# RFnetwork.net
KiCad netlist of a schematic drawn in Altium Designer
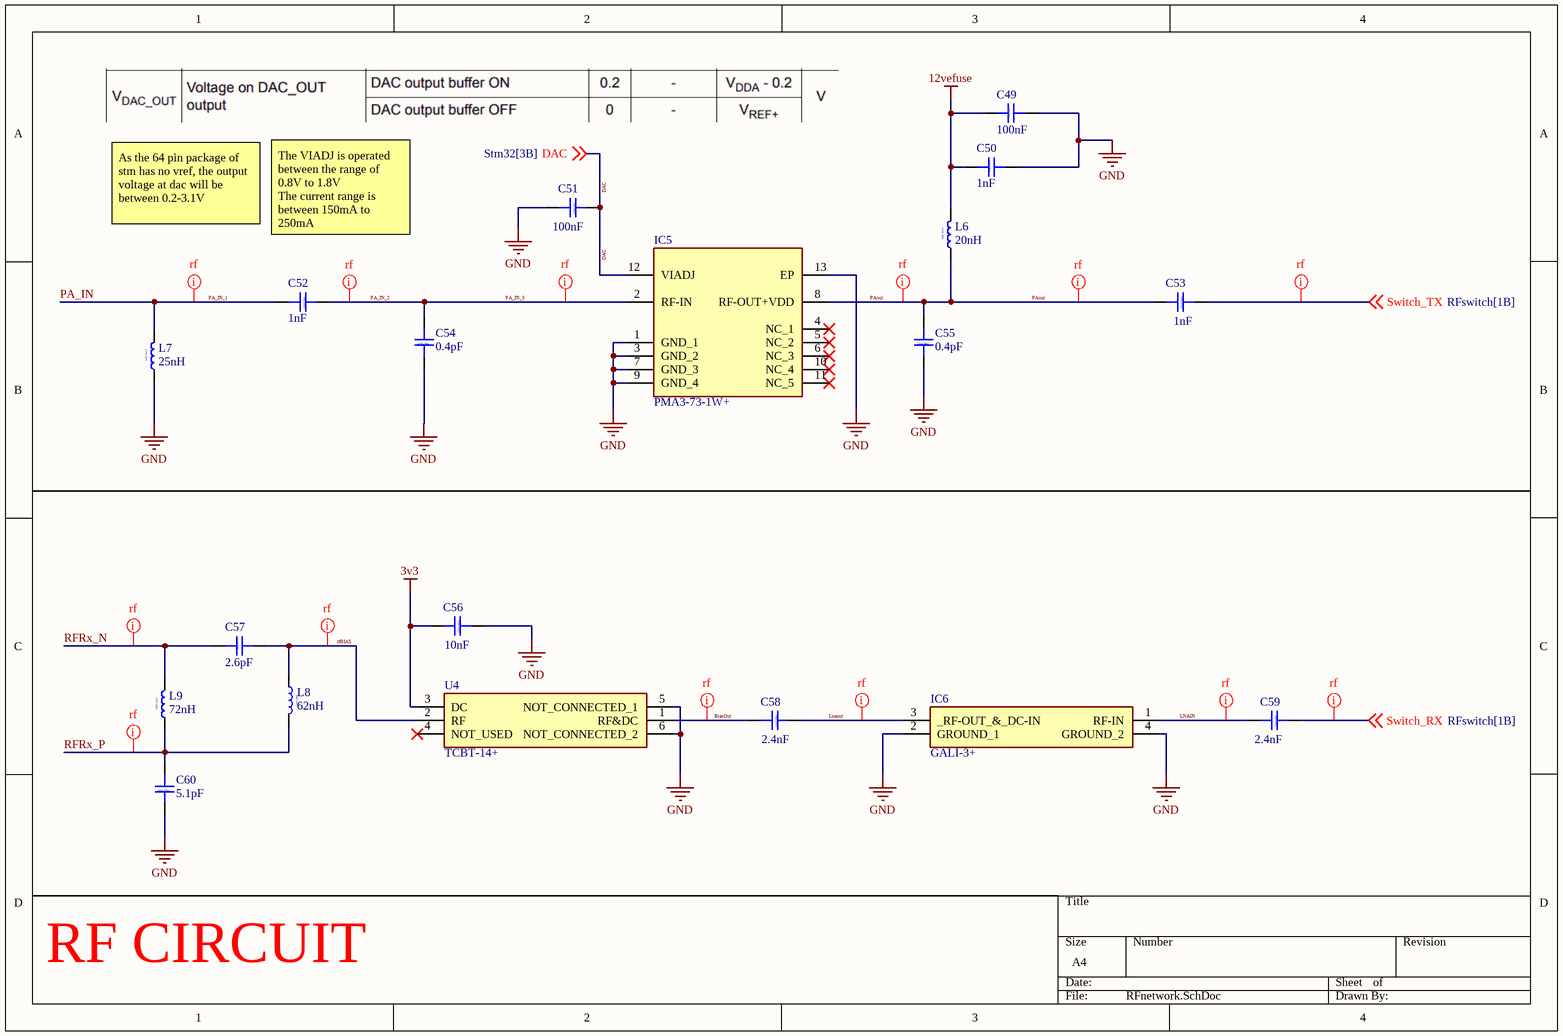
[diagram p0: RFnetwork.SchDoc]

(export (version "E")
  (design (tool "Eeschema 10.0.6"))
  (components
    (comp (ref "C49")
      (value "100nF")
      (footprint "CAP_0603")
      (description "Capacitor SMD 0603 RATED")
      (libsource (lib "STeRG-Passives-Standard") (part "Capacitor-SMD-0603"))
    )
    (comp (ref "C50")
      (value "1nF")
      (footprint "CAP_0603")
      (description "Capacitor SMD 0603 RATED")
      (libsource (lib "STeRG-Passives-Standard") (part "Capacitor-SMD-0603"))
    )
    (comp (ref "C51")
      (value "100nF")
      (footprint "CAP_0603")
      (description "Capacitor SMD 0603 RATED")
      (libsource (lib "STeRG-Passives-Standard") (part "Capacitor-SMD-0603"))
    )
    (comp (ref "C52")
      (value "1nF")
      (footprint "CAP_0603")
      (description "Capacitor SMD 0603 RATED")
      (libsource (lib "STeRG-Passives-Standard") (part "Capacitor-SMD-0603"))
    )
    (comp (ref "C53")
      (value "1nF")
      (footprint "CAP_0603")
      (description "Capacitor SMD 0603 RATED")
      (libsource (lib "STeRG-Passives-Standard") (part "Capacitor-SMD-0603"))
    )
    (comp (ref "C54")
      (value "0.4pF")
      (footprint "CAP_0603")
      (description "Capacitor SMD 0603 RATED")
      (libsource (lib "STeRG-Passives-Standard") (part "Capacitor-SMD-0603"))
    )
    (comp (ref "C55")
      (value "0.4pF")
      (footprint "CAP_0603")
      (description "Capacitor SMD 0603 RATED")
      (libsource (lib "STeRG-Passives-Standard") (part "Capacitor-SMD-0603"))
    )
    (comp (ref "C56")
      (value "10nF")
      (footprint "CAP_0603")
      (description "Capacitor SMD 0603 RATED")
      (libsource (lib "STeRG-Passives-Standard") (part "Capacitor-SMD-0603"))
    )
    (comp (ref "C57")
      (value "2.6pF")
      (footprint "CAP_0402")
      (description "Capacitor SMD 0402 RATED")
      (libsource (lib "STeRG-Passives-Standard") (part "Capacitor-SMD-0402"))
    )
    (comp (ref "C58")
      (value "2.4nF")
      (footprint "CAP_0603")
      (description "Capacitor SMD 0603 RATED")
      (libsource (lib "STeRG-Passives-Standard") (part "Capacitor-SMD-0603"))
    )
    (comp (ref "C59")
      (value "2.4nF")
      (footprint "CAP_0603")
      (description "Capacitor SMD 0603 RATED")
      (libsource (lib "STeRG-Passives-Standard") (part "Capacitor-SMD-0603"))
    )
    (comp (ref "C60")
      (value "5.1pF")
      (footprint "CAP_0402")
      (description "Capacitor SMD 0402 RATED")
      (libsource (lib "STeRG-Passives-Standard") (part "Capacitor-SMD-0402"))
    )
    (comp (ref "IC5")
      (value "PMA3-73-1W+")
      (footprint "SamacSys:QFN51P300X300X89-13N")
      (description "Integrated Circuit")
      (libsource (lib "SamacSys") (part "PMA3-73-1W+"))
    )
    (comp (ref "IC6")
      (value "GALI-3+")
      (footprint "GALI3")
      (description "Integrated Circuit")
      (fields (field (name "MOUSER PART NUMBER") "139-GALI-3"))
      (libsource (lib "SamacSys") (part "GALI-3+"))
    )
    (comp (ref "L6")
      (value "20nH")
      (footprint "IND_0603")
      (description "Inductor SMD 0603")
      (libsource (lib "STeRG-Passives-Standard") (part "Inductor-SMD-RF-0603"))
    )
    (comp (ref "L7")
      (value "25nH")
      (footprint "IND_0603")
      (description "Inductor SMD 0603")
      (libsource (lib "STeRG-Passives-Standard") (part "Inductor-SMD-RF-0603"))
    )
    (comp (ref "L8")
      (value "62nH")
      (footprint "IND_0402")
      (description "Inductor SMD 0402")
      (libsource (lib "STeRG-Passives-Standard") (part "Inductor-SMD-RF-0402"))
    )
    (comp (ref "L9")
      (value "72nH")
      (footprint "IND_0402")
      (description "Inductor SMD 0402")
      (libsource (lib "STeRG-Passives-Standard") (part "Inductor-SMD-RF-0402"))
    )
    (comp (ref "U4")
      (value "TCBT-14+")
      (footprint "TCBT14bias")
      (description "Undefined or Miscellaneous")
      (fields (field (name "MOUSER PART NUMBER") "139-TCBT-14"))
      (libsource (lib "SamacSys") (part "TCBT-14+"))
    )
  )
  (nets
    (net (code "1") (name "/BiasOut") (class "Default")
      (node (ref "C58") (pin "2") (pinfunction "2_2") (pintype "passive"))
      (node (ref "U4") (pin "1") (pinfunction "RF&DC_1") (pintype "passive"))
    )
    (net (code "2") (name "/LNAIN") (class "Default")
      (node (ref "C59") (pin "2") (pinfunction "2_2") (pintype "passive"))
      (node (ref "IC6") (pin "1") (pinfunction "RF-IN_1") (pintype "passive"))
    )
    (net (code "3") (name "/Lnaout") (class "Default")
      (node (ref "C58") (pin "1") (pinfunction "1_1") (pintype "passive"))
      (node (ref "IC6") (pin "3") (pinfunction "_RF-OUT_&_DC-IN_3") (pintype "passive"))
    )
    (net (code "4") (name "/PA_IN") (class "Default")
      (node (ref "C52") (pin "2") (pinfunction "2_2") (pintype "passive"))
      (node (ref "L7") (pin "2") (pinfunction "2_2") (pintype "passive"))
    )
    (net (code "5") (name "/PA_IN_2") (class "Default")
      (node (ref "C52") (pin "1") (pinfunction "1_1") (pintype "passive"))
      (node (ref "C54") (pin "2") (pinfunction "2_2") (pintype "passive"))
      (node (ref "IC5") (pin "2") (pinfunction "RF-IN_2") (pintype "passive"))
    )
    (net (code "6") (name "/PAout") (class "Default")
      (node (ref "C53") (pin "2") (pinfunction "2_2") (pintype "passive"))
      (node (ref "C55") (pin "2") (pinfunction "2_2") (pintype "passive"))
      (node (ref "IC5") (pin "8") (pinfunction "RF-OUT+VDD_8") (pintype "passive"))
      (node (ref "L6") (pin "1") (pinfunction "1_1") (pintype "passive"))
    )
    (net (code "7") (name "/RFRx_N") (class "Default")
      (node (ref "C57") (pin "1") (pinfunction "1_1") (pintype "passive"))
      (node (ref "L9") (pin "2") (pinfunction "2_2") (pintype "passive"))
    )
    (net (code "8") (name "/RFRx_P") (class "Default")
      (node (ref "C60") (pin "2") (pinfunction "2_2") (pintype "passive"))
      (node (ref "L8") (pin "2") (pinfunction "2_2") (pintype "passive"))
      (node (ref "L9") (pin "1") (pinfunction "1_1") (pintype "passive"))
    )
    (net (code "9") (name "/rfBIAS") (class "Default")
      (node (ref "C57") (pin "2") (pinfunction "2_2") (pintype "passive"))
      (node (ref "L8") (pin "1") (pinfunction "1_1") (pintype "passive"))
      (node (ref "U4") (pin "2") (pinfunction "RF_2") (pintype "passive"))
    )
    (net (code "10") (name "3v3") (class "Default")
      (node (ref "C56") (pin "2") (pinfunction "2_2") (pintype "passive"))
      (node (ref "U4") (pin "3") (pinfunction "DC_3") (pintype "passive"))
    )
    (net (code "11") (name "12vefuse") (class "Default")
      (node (ref "C49") (pin "1") (pinfunction "1_1") (pintype "passive"))
      (node (ref "C50") (pin "1") (pinfunction "1_1") (pintype "passive"))
      (node (ref "L6") (pin "2") (pinfunction "2_2") (pintype "passive"))
    )
    (net (code "12") (name "DAC") (class "Default")
      (node (ref "C51") (pin "1") (pinfunction "1_1") (pintype "passive"))
      (node (ref "IC5") (pin "12") (pinfunction "VIADJ_12") (pintype "passive"))
    )
    (net (code "13") (name "GND") (class "Default")
      (node (ref "C49") (pin "2") (pinfunction "2_2") (pintype "passive"))
      (node (ref "C50") (pin "2") (pinfunction "2_2") (pintype "passive"))
      (node (ref "C51") (pin "2") (pinfunction "2_2") (pintype "passive"))
      (node (ref "C54") (pin "1") (pinfunction "1_1") (pintype "passive"))
      (node (ref "C55") (pin "1") (pinfunction "1_1") (pintype "passive"))
      (node (ref "C56") (pin "1") (pinfunction "1_1") (pintype "passive"))
      (node (ref "C60") (pin "1") (pinfunction "1_1") (pintype "passive"))
      (node (ref "IC5") (pin "1") (pinfunction "GND_1_1") (pintype "passive"))
      (node (ref "IC5") (pin "13") (pinfunction "EP_13") (pintype "passive"))
      (node (ref "IC5") (pin "3") (pinfunction "GND_2_3") (pintype "passive"))
      (node (ref "IC5") (pin "7") (pinfunction "GND_3_7") (pintype "passive"))
      (node (ref "IC5") (pin "9") (pinfunction "GND_4_9") (pintype "passive"))
      (node (ref "IC6") (pin "2") (pinfunction "GROUND_1_2") (pintype "passive"))
      (node (ref "IC6") (pin "4") (pinfunction "GROUND_2_4") (pintype "passive"))
      (node (ref "L7") (pin "1") (pinfunction "1_1") (pintype "passive"))
      (node (ref "U4") (pin "5") (pinfunction "NOT_CONNECTED_1_5") (pintype "passive"))
      (node (ref "U4") (pin "6") (pinfunction "NOT_CONNECTED_2_6") (pintype "passive"))
    )
    (net (code "14") (name "Switch_RX") (class "Default")
      (node (ref "C59") (pin "1") (pinfunction "1_1") (pintype "passive"))
    )
    (net (code "15") (name "Switch_TX") (class "Default")
      (node (ref "C53") (pin "1") (pinfunction "1_1") (pintype "passive"))
    )
    (net (code "16") (name "unconnected-(IC5-NC_1-Pad4)") (class "Default")
      (node (ref "IC5") (pin "4") (pinfunction "NC_1_4") (pintype "passive+no_connect"))
    )
    (net (code "17") (name "unconnected-(IC5-NC_2-Pad5)") (class "Default")
      (node (ref "IC5") (pin "5") (pinfunction "NC_2_5") (pintype "passive+no_connect"))
    )
    (net (code "18") (name "unconnected-(IC5-NC_3-Pad6)") (class "Default")
      (node (ref "IC5") (pin "6") (pinfunction "NC_3_6") (pintype "passive+no_connect"))
    )
    (net (code "19") (name "unconnected-(IC5-NC_4-Pad10)") (class "Default")
      (node (ref "IC5") (pin "10") (pinfunction "NC_4_10") (pintype "passive+no_connect"))
    )
    (net (code "20") (name "unconnected-(IC5-NC_5-Pad11)") (class "Default")
      (node (ref "IC5") (pin "11") (pinfunction "NC_5_11") (pintype "passive+no_connect"))
    )
    (net (code "21") (name "unconnected-(U4-NOT_USED-Pad4)") (class "Default")
      (node (ref "U4") (pin "4") (pinfunction "NOT_USED_4") (pintype "passive+no_connect"))
    )
  )
)
